# schematicFingerprint.net
KiCad netlist of a schematic drawn in Altium Designer
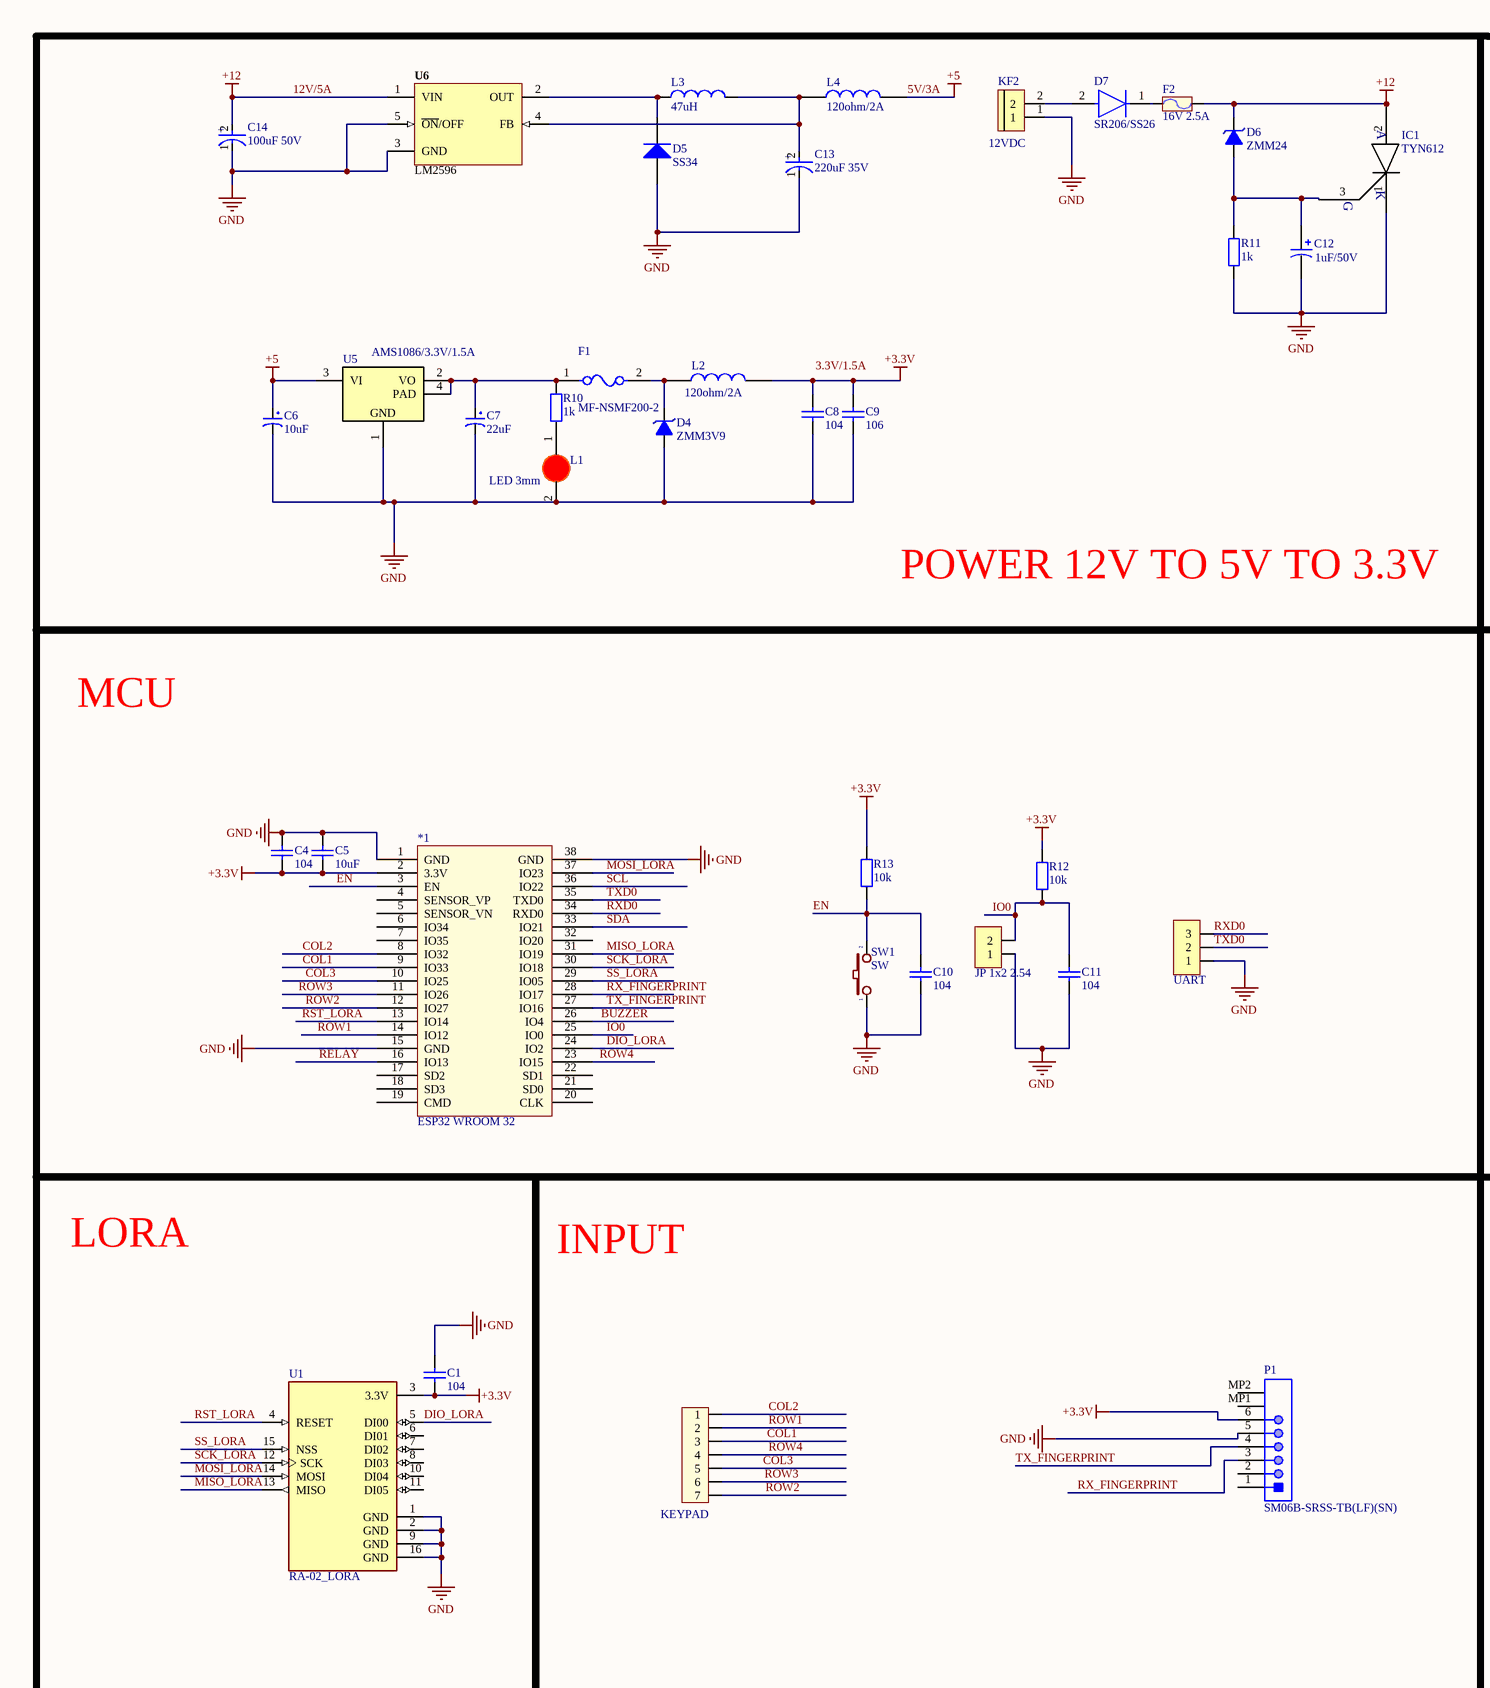
[diagram p0: schematicFingerprint.SchDoc, left]
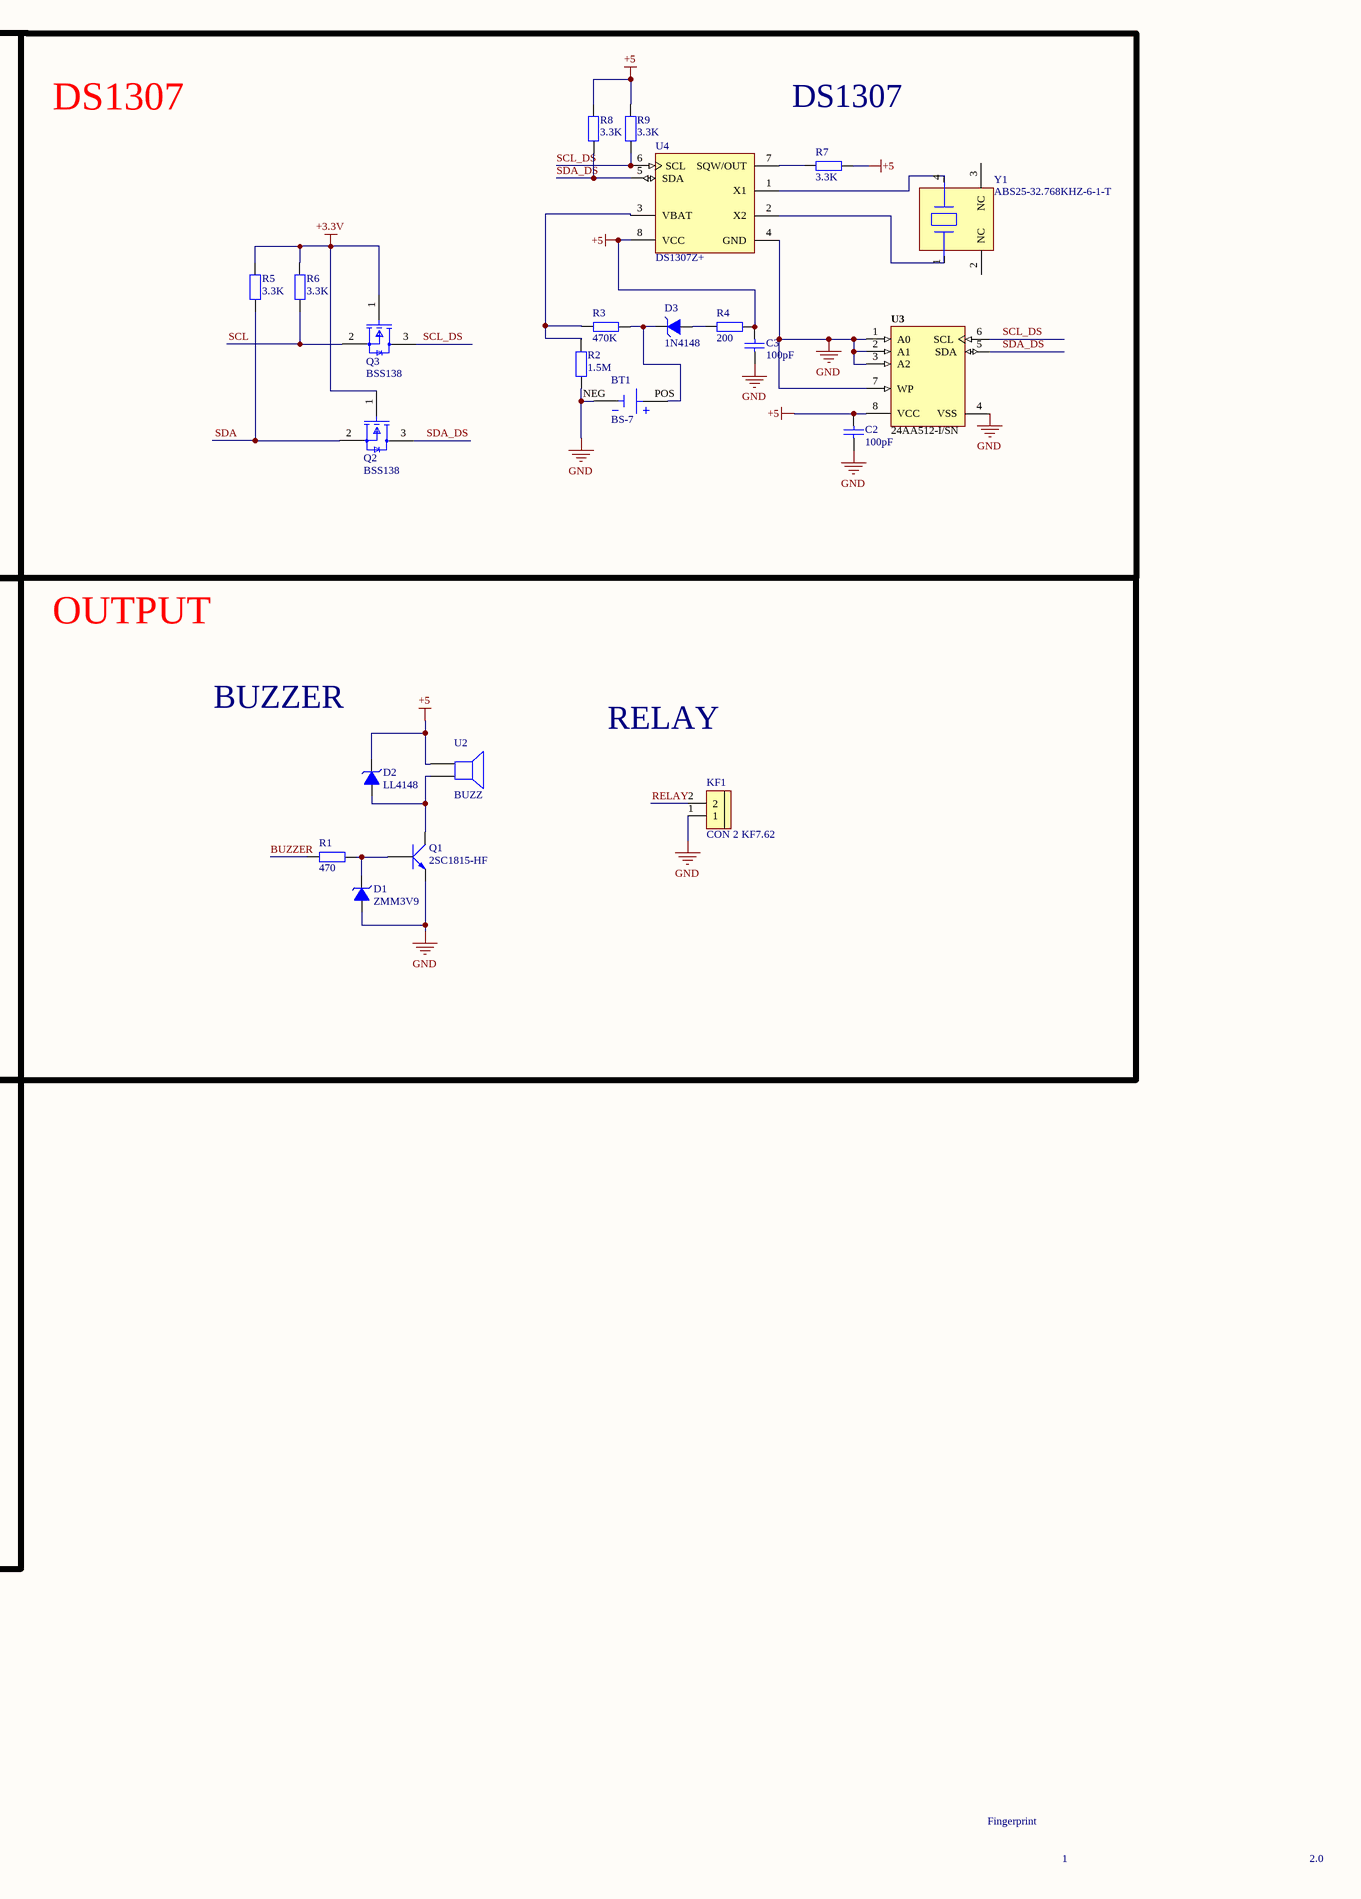
[diagram p1: schematicFingerprint.SchDoc, right]

(export (version "E")
  (design (tool "Eeschema 10.0.6"))
  (components
    (comp (ref "*1")
      (value "ESP32 WROOM 32")
      (footprint "ESP32-WROOM-32D")
      (libsource (lib "Altium_Lib_by_KhueNguyenCreator") (part "ESP32 WROOM 32"))
    )
    (comp (ref "BT1")
      (value "BS-7")
      (footprint "BAT_BS-7")
      (description "BATTERY HOLDER COIN 20MM PC PIN")
      (fields (field (name "MF") "MPD _Memory"))
      (libsource (lib "Integrated_Library") (part "BS-7"))
    )
    (comp (ref "C1")
      (value "104")
      (footprint "tu 0805")
      (description "Dán")
      (libsource (lib "Altium_Lib_by_KhueNguyenCreator") (part "Tu 0805 104 50V 10%"))
    )
    (comp (ref "C2")
      (value "100pF")
      (footprint "tu 0805")
      (description "Dán")
      (libsource (lib "Altium_Lib_by_KhueNguyenCreator") (part "Tu 0805 104 50V 10%"))
    )
    (comp (ref "C3")
      (value "100pF")
      (footprint "tu 0805")
      (description "Dán")
      (libsource (lib "Altium_Lib_by_KhueNguyenCreator") (part "Tu 0805 104 50V 10%"))
    )
    (comp (ref "C4")
      (value "104")
      (footprint "tu 0805")
      (description "Dán")
      (libsource (lib "Altium_Lib_by_KhueNguyenCreator") (part "Tu 0805 104 50V 10%"))
    )
    (comp (ref "C5")
      (value "10uF")
      (footprint "tu 0805")
      (description "Dán")
      (libsource (lib "Altium_Lib_by_KhueNguyenCreator") (part "Tu 0805 104 50V 10%"))
    )
    (comp (ref "C6")
      (value "10uF")
      (footprint "tu tantalum smd6032")
      (description "Dán")
      (libsource (lib "Altium_Lib_by_KhueNguyenCreator") (part "Tu tantalum 10uF 35V SMD6032"))
    )
    (comp (ref "C7")
      (value "22uF")
      (footprint "tu tantalum smd6032")
      (description "Dán")
      (libsource (lib "Altium_Lib_by_KhueNguyenCreator") (part "Tu tantalum 22uF 25V SMD6032"))
    )
    (comp (ref "C8")
      (value "104")
      (footprint "tu 0805")
      (description "Dán")
      (libsource (lib "Altium_Lib_by_KhueNguyenCreator") (part "Tu 0805 104 50V 10%"))
    )
    (comp (ref "C9")
      (value "106")
      (footprint "tu 0805")
      (description "Dán")
      (libsource (lib "Altium_Lib_by_KhueNguyenCreator") (part "Tu 0805 106 16V 10%"))
    )
    (comp (ref "C10")
      (value "104")
      (footprint "tu 0805")
      (description "Dán")
      (libsource (lib "Altium_Lib_by_KhueNguyenCreator") (part "Tu 0805 104 50V 10%"))
    )
    (comp (ref "C11")
      (value "104")
      (footprint "tu 0805")
      (description "Dán")
      (libsource (lib "Altium_Lib_by_KhueNguyenCreator") (part "Tu 0805 104 50V 10%"))
    )
    (comp (ref "C12")
      (value "1uF/50V")
      (footprint "CAP_ALUM_SMD_4054_TYPE_B")
      (description "CAP ALUM 10uF 20% 16V SMD")
      (fields (field (name "MPN") "EEE-HA1C100P") (field (name "MFR") "Panasonic"))
      (libsource (lib "BYTECH_HW_LIB_2019 ") (part "EEE-HA1C100P"))
    )
    (comp (ref "C13")
      (value "220uF 35V")
      (footprint "FP-SGV8X10_5-MFG")
      (description "CAP ALUM 100UF 20% 50V SMD")
      (fields (field (name "VOLTAGE") "50V") (field (name "TOLERANCE") "20%"))
      (libsource (lib "Altium Content Vault") (part "203bc49f2ac43e59fd269a8c329ed05"))
    )
    (comp (ref "C14")
      (value "100uF 50V")
      (footprint "FP-SGV8X10_5-MFG")
      (description "CAP ALUM 100UF 20% 50V SMD")
      (fields (field (name "VOLTAGE") "50V") (field (name "TOLERANCE") "20%"))
      (libsource (lib "Altium Content Vault") (part "203bc49f2ac43e59fd269a8c329ed05"))
    )
    (comp (ref "D1")
      (value "ZMM3V9")
      (footprint "DIODE ZENNER SMD SOD80")
      (description "Dán")
      (libsource (lib "Altium_Lib_by_KhueNguyenCreator") (part "Diode Zener 3.3V"))
    )
    (comp (ref "D2")
      (value "LL4148")
      (footprint "DIODE ZENNER SMD SOD80")
      (description "Dán")
      (libsource (lib "Altium_Lib_by_KhueNguyenCreator") (part "Diode Zener 3.3V"))
    )
    (comp (ref "D3")
      (value "1N4148")
      (footprint "DIODE ZENNER SMD SOD80")
      (description "Dán")
      (libsource (lib "Altium_Lib_by_KhueNguyenCreator") (part "Diode Zener 3.3V"))
    )
    (comp (ref "D4")
      (value "ZMM3V9")
      (footprint "DIODE ZENNER SMD SOD80")
      (description "Dán")
      (libsource (lib "Altium_Lib_by_KhueNguyenCreator") (part "Diode Zener 3.3V"))
    )
    (comp (ref "D5")
      (value "SS34")
      (footprint "DIODE SMA")
      (description "Dán")
      (libsource (lib "Altium_Lib_by_KhueNguyenCreator") (part "Diode SS34 ( 1N5822 )"))
    )
    (comp (ref "D6")
      (value "ZMM24")
      (footprint "DIODE ZENNER SMD SOD80")
      (description "Dán")
      (libsource (lib "Altium_Lib_by_KhueNguyenCreator") (part "Diode Zener 15V"))
    )
    (comp (ref "D7")
      (value "SR206/SS26")
      (footprint "FP-95401-MFG")
      (description "DIODE GEN PURP 600V 2A DO214AA")
      (libsource (lib "Altium Content Vault") (part "d7152d700b627762746794eb795d46e"))
    )
    (comp (ref "F1")
      (value "MF-NSMF200-2")
      (footprint "FP-MF-NSMF200-2-MFG")
      (description "PTC RESET FUSE 6V 2A 1206")
      (fields
        (field (name "MANUFACTURER") "Bourns Inc.")
        (field (name "OCTOPART") "https://octopart.com/mf-nsmf200-2-bourns-90790")
      )
      (libsource (lib "Altium Content Vault") (part "5bcf9b9f640e542cf0359d10258e979"))
    )
    (comp (ref "F2")
      (value "16V 2.5A")
      (footprint "Cau chi tu phuc hoi 2A 24V SMD1812")
      (description "2A 24V SMD1812")
      (libsource (lib "Altium_Lib_by_KhueNguyenCreator") (part "Cau chi tu phuc hoi 2A 24V SMD1812"))
    )
    (comp (ref "H1")
      (value "KEYPAD")
      (footprint "Header 7P DC 2.54")
      (description "Cắm")
      (libsource (lib "Altium_Lib_by_KhueNguyenCreator") (part "Header 7P 2.54 Duc Cong"))
    )
    (comp (ref "IC1")
      (value "TYN612")
      (footprint "PCBComponent_1")
      (libsource (lib "Integrated_Library1") (part "TYN612"))
    )
    (comp (ref "JP1")
      (value "JP 1x2 2.54")
      (footprint "JP 1x2 DT")
      (description "Cắm")
      (libsource (lib "Altium_Lib_by_KhueNguyenCreator") (part "JP 1x2 2.54 Duc Thang"))
    )
    (comp (ref "JP2")
      (value "UART")
      (footprint "JP 1x3 DT")
      (description "Cắm")
      (libsource (lib "Altium_Lib_by_KhueNguyenCreator") (part "JP 1x3 2.54 Duc Thang"))
    )
    (comp (ref "KF1")
      (value "CON 2 KF7.62")
      (footprint "CON 2 KF7.62")
      (description "Cắm")
      (libsource (lib "Altium_Lib_by_KhueNguyenCreator") (part "CON 2 KF7.62"))
    )
    (comp (ref "KF2")
      (value "12VDC")
      (footprint "CON 2 KF7.62")
      (description "Cắm")
      (libsource (lib "") (part "CON 2 KF7.62_1"))
    )
    (comp (ref "L1")
      (value "LED 3mm")
      (footprint "LED-3MM-RED")
      (description "Cắm")
      (libsource (lib "Altium_Lib_by_KhueNguyenCreator") (part "LED 3mm Do"))
    )
    (comp (ref "L2")
      (value "120ohm/2A")
      (footprint "IND-0805 (2012)")
      (description "2A 120 OHM 0805")
      (fields (field (name "MPN") "742792042"))
      (libsource (lib "BYTECH_HW_LIB_2019 ") (part "742792042"))
    )
    (comp (ref "L3")
      (value "47uH")
      (footprint "SUMI-CDRH127_V")
      (description "Power Inductor, 10 uH, +/- 20%, -40 to 100 degC, 2-Pin SMD, RoHS, Tape and Reel")
      (fields (field (name "MANUFACTURER") "Sumida") (field (name "TOLERANCE") "±20%"))
      (libsource (lib "Altium Content Vault") (part "IND-2"))
    )
    (comp (ref "L4")
      (value "120ohm/2A")
      (footprint "IND-0805 (2012)")
      (description "2A 120 OHM 0805")
      (fields (field (name "MPN") "742792042"))
      (libsource (lib "BYTECH_HW_LIB_2019 ") (part "742792042"))
    )
    (comp (ref "P1")
      (value "SM06B-SRSS-TB(LF)(SN)")
      (footprint "JST-SM06B-SRSS-TB_V")
      (description "Male Header, Pitch 1 mm, 1 x 6 Position, Height 2.95 mm, -25 to 85 degC, RoHS, Tape and Reel")
      (fields (field (name "MANUFACTURER") "JST"))
      (libsource (lib "Altium Content Vault") (part "CN-1P-2M-R6"))
    )
    (comp (ref "Q1")
      (value "2SC1815-HF")
      (footprint "SOT23")
      (description "NPN transistor")
      (libsource (lib "Altium_Lib_by_KhueNguyenCreator") (part "C1815 HF SMD"))
    )
    (comp (ref "Q2")
      (value "BSS138")
      (footprint "FP-318-08-IPC_A")
      (description "MOSFET N-CH 50V 220MA SOT-23")
      (libsource (lib "Altium Content Vault") (part "3b9c635fedb024a5347a57b145af9cc"))
    )
    (comp (ref "Q3")
      (value "BSS138")
      (footprint "FP-318-08-IPC_A")
      (description "MOSFET N-CH 50V 220MA SOT-23")
      (libsource (lib "Altium Content Vault") (part "3b9c635fedb024a5347a57b145af9cc"))
    )
    (comp (ref "R1")
      (value "470")
      (footprint "tro smd 0805")
      (description "Dán")
      (libsource (lib "Altium_Lib_by_KhueNguyenCreator") (part "Tro 0805 1% 470k"))
    )
    (comp (ref "R2")
      (value "1.5M")
      (footprint "tro smd 0805")
      (description "Dán")
      (libsource (lib "Altium_Lib_by_KhueNguyenCreator") (part "Tro 0805 5% 10k"))
    )
    (comp (ref "R3")
      (value "470K")
      (footprint "tro smd 0805")
      (description "Dán")
      (libsource (lib "Altium_Lib_by_KhueNguyenCreator") (part "Tro 0805 5% 10k"))
    )
    (comp (ref "R4")
      (value "200")
      (footprint "tro smd 0805")
      (description "Dán")
      (libsource (lib "Altium_Lib_by_KhueNguyenCreator") (part "Tro 0805 5% 10k"))
    )
    (comp (ref "R5")
      (value "3.3K")
      (footprint "tro smd 0805")
      (description "Dán")
      (libsource (lib "Altium_Lib_by_KhueNguyenCreator") (part "Tro 0805 5% 10k"))
    )
    (comp (ref "R6")
      (value "3.3K")
      (footprint "tro smd 0805")
      (description "Dán")
      (libsource (lib "Altium_Lib_by_KhueNguyenCreator") (part "Tro 0805 5% 10k"))
    )
    (comp (ref "R7")
      (value "3.3K")
      (footprint "tro smd 0805")
      (description "Dán")
      (libsource (lib "Altium_Lib_by_KhueNguyenCreator") (part "Tro 0805 5% 10k"))
    )
    (comp (ref "R8")
      (value "3.3K")
      (footprint "tro smd 0805")
      (description "Dán")
      (libsource (lib "Altium_Lib_by_KhueNguyenCreator") (part "Tro 0805 5% 10k"))
    )
    (comp (ref "R9")
      (value "3.3K")
      (footprint "tro smd 0805")
      (description "Dán")
      (libsource (lib "Altium_Lib_by_KhueNguyenCreator") (part "Tro 0805 5% 10k"))
    )
    (comp (ref "R10")
      (value "1k")
      (footprint "tro smd 0805")
      (description "Dán")
      (libsource (lib "Altium_Lib_by_KhueNguyenCreator") (part "Tro 0805 1% 1k"))
    )
    (comp (ref "R11")
      (value "1k")
      (footprint "tro smd 0805")
      (description "Dán")
      (libsource (lib "Altium_Lib_by_KhueNguyenCreator") (part "Tro 0805 1% 1k"))
    )
    (comp (ref "R12")
      (value "10k")
      (footprint "tro smd 0805")
      (description "Dán")
      (libsource (lib "Altium_Lib_by_KhueNguyenCreator") (part "Tro 0805 5% 10k"))
    )
    (comp (ref "R13")
      (value "10k")
      (footprint "tro smd 0805")
      (description "Dán")
      (libsource (lib "Altium_Lib_by_KhueNguyenCreator") (part "Tro 0805 5% 10k"))
    )
    (comp (ref "SW1")
      (value "SW")
      (footprint "SW1-SMD")
      (description "Switch button 2 pin")
      (libsource (lib "TechMT.VN_Lib_Project v2") (part "SW2"))
    )
    (comp (ref "U1")
      (value "RA-02_LORA")
      (footprint "MODULE_RA-02_LORA")
      (description "Ra-02 LoRa RF M5Stack Platform Evaluation Expansion Board")
      (fields (field (name "MP") "Ra-02 LoRa") (field (name "MF") "AI-Thinker"))
      (libsource (lib "Integrated_Library1") (part "RA-02_LORA"))
    )
    (comp (ref "U2")
      (value "BUZZ")
      (footprint "BUZZER_through_hole")
      (description "Loudspeaker")
      (libsource (lib "BYTECH_HW_LIB_2019 ") (part "Speaker"))
    )
    (comp (ref "U3")
      (value "24AA512-I/SN")
      (footprint "SO8")
      (description "512K bits I2C™ Serial EEPROM, 1.7 to 5.5 V, 400 kHz, -40 to 85 degC, 8-pin SOIC (SN8), Tube")
      (fields (field (name "MANUFACTURER") "Microchip"))
      (libsource (lib "TechMT.VN_Lib_Project v2") (part "24-AA-FC512-SOIC-TSSOP-8"))
    )
    (comp (ref "U4")
      (value "DS1307Z+")
      (footprint "S8+2_L")
      (description "64 x 8, Serial, I2C Real-Time Clock, 5.0V, 8-Pin SO, 0 to 70 degC, Pb-Free")
      (libsource (lib "Altium Content Vault") (part "PR_RTC_DS1307-IL8"))
    )
    (comp (ref "U5")
      (value "AMS1086/3.3V/1.5A")
      (footprint "TO-263-3_102_433_181X45_SMD")
      (description "Linear Voltage Regulator IC 1 Output 5A DDPAK/TO-263-3")
      (fields
        (field (name "MANUFACTURER") "STMicroelectronics")
        (field (name "MANUFACTURER PART NUMBER") "LM1084ISX-3.3/NOPB")
      )
      (libsource (lib "Altium_Lib_by_KhueNguyenCreator") (part "REG_27V-3.3V-5A-30W-TO-263_1"))
    )
    (comp (ref "U6")
      (value "LM2596")
      (footprint "TO263")
      (libsource (lib "TechMT.VN_Lib_Project v2") (part "LM2596"))
    )
    (comp (ref "Y1")
      (value "ABS25-32.768KHZ-6-1-T")
      (footprint "FP-ABS25-MFG")
      (description "CRYSTAL 32.7680KHZ 6PF SMD")
      (fields (field (name "TOLERANCE") "10ppm"))
      (libsource (lib "Altium Content Vault") (part "28be33c29b20f54059194caee89ade4"))
    )
  )
  (nets
    (net (code "1") (name "+3.3V") (class "Default")
      (node (ref "*1") (pin "2") (pinfunction "3.3V_2") (pintype "passive"))
      (node (ref "C1") (pin "2") (pinfunction "2_2") (pintype "passive"))
      (node (ref "C4") (pin "1") (pinfunction "1_1") (pintype "passive"))
      (node (ref "C5") (pin "1") (pinfunction "1_1") (pintype "passive"))
      (node (ref "C8") (pin "1") (pinfunction "1_1") (pintype "passive"))
      (node (ref "C9") (pin "1") (pinfunction "1_1") (pintype "passive"))
      (node (ref "L2") (pin "2") (pinfunction "2_2") (pintype "passive"))
      (node (ref "P1") (pin "6") (pinfunction "6_6") (pintype "passive"))
      (node (ref "Q2") (pin "1") (pinfunction "G_1") (pintype "passive"))
      (node (ref "Q3") (pin "1") (pinfunction "G_1") (pintype "passive"))
      (node (ref "R12") (pin "1") (pinfunction "1_1") (pintype "passive"))
      (node (ref "R13") (pin "1") (pinfunction "1_1") (pintype "passive"))
      (node (ref "R5") (pin "1") (pinfunction "1_1") (pintype "passive"))
      (node (ref "R6") (pin "1") (pinfunction "1_1") (pintype "passive"))
      (node (ref "U1") (pin "3") (pinfunction "3.3V_3") (pintype "power_in"))
    )
    (net (code "2") (name "+5") (class "Default")
      (node (ref "C2") (pin "2") (pinfunction "2_2") (pintype "passive"))
      (node (ref "C3") (pin "2") (pinfunction "2_2") (pintype "passive"))
      (node (ref "C6") (pin "1") (pinfunction "1_1") (pintype "passive"))
      (node (ref "D2") (pin "2") (pinfunction "K_2") (pintype "passive"))
      (node (ref "L4") (pin "2") (pinfunction "2_2") (pintype "passive"))
      (node (ref "R4") (pin "2") (pinfunction "2_2") (pintype "passive"))
      (node (ref "R7") (pin "2") (pinfunction "2_2") (pintype "passive"))
      (node (ref "R8") (pin "1") (pinfunction "1_1") (pintype "passive"))
      (node (ref "R9") (pin "1") (pinfunction "1_1") (pintype "passive"))
      (node (ref "U2") (pin "1") (pinfunction "1_1") (pintype "passive"))
      (node (ref "U3") (pin "8") (pinfunction "VCC_8") (pintype "power_in"))
      (node (ref "U4") (pin "8") (pinfunction "VCC_8") (pintype "power_in"))
      (node (ref "U5") (pin "3") (pinfunction "VI_3") (pintype "passive"))
    )
    (net (code "3") (name "+12") (class "Default")
      (node (ref "C14") (pin "2") (pinfunction "A_2") (pintype "passive"))
      (node (ref "D6") (pin "2") (pinfunction "K_2") (pintype "passive"))
      (node (ref "F2") (pin "2") (pinfunction "2_2") (pintype "passive"))
      (node (ref "IC1") (pin "2") (pinfunction "A_2") (pintype "passive"))
      (node (ref "U6") (pin "1") (pinfunction "VIN_1") (pintype "power_in"))
    )
    (net (code "5") (name "/BUZZER") (class "Default")
      (node (ref "*1") (pin "26") (pinfunction "IO4_26") (pintype "passive"))
      (node (ref "R1") (pin "1") (pinfunction "1_1") (pintype "passive"))
    )
    (net (code "6") (name "/COL1") (class "Default")
      (node (ref "*1") (pin "9") (pinfunction "IO33_9") (pintype "passive"))
      (node (ref "H1") (pin "3") (pinfunction "3_3") (pintype "passive"))
    )
    (net (code "7") (name "/COL2") (class "Default")
      (node (ref "*1") (pin "8") (pinfunction "IO32_8") (pintype "passive"))
      (node (ref "H1") (pin "1") (pinfunction "1_1") (pintype "passive"))
    )
    (net (code "8") (name "/COL3") (class "Default")
      (node (ref "*1") (pin "10") (pinfunction "IO25_10") (pintype "passive"))
      (node (ref "H1") (pin "5") (pinfunction "5_5") (pintype "passive"))
    )
    (net (code "9") (name "/DIO_LORA") (class "Default")
      (node (ref "*1") (pin "24") (pinfunction "IO2_24") (pintype "passive"))
      (node (ref "U1") (pin "5") (pinfunction "DI00_5") (pintype "bidirectional"))
    )
    (net (code "10") (name "/EN") (class "Default")
      (node (ref "*1") (pin "3") (pinfunction "EN_3") (pintype "passive"))
      (node (ref "C10") (pin "2") (pinfunction "2_2") (pintype "passive"))
      (node (ref "R13") (pin "2") (pinfunction "2_2") (pintype "passive"))
      (node (ref "SW1") (pin "2") (pinfunction "2_2") (pintype "passive"))
    )
    (net (code "11") (name "/IO0") (class "Default")
      (node (ref "*1") (pin "25") (pinfunction "IO0_25") (pintype "passive"))
      (node (ref "C11") (pin "2") (pinfunction "2_2") (pintype "passive"))
      (node (ref "JP1") (pin "2") (pinfunction "2_2") (pintype "passive"))
      (node (ref "R12") (pin "2") (pinfunction "2_2") (pintype "passive"))
    )
    (net (code "12") (name "/MISO_LORA") (class "Default")
      (node (ref "*1") (pin "31") (pinfunction "IO19_31") (pintype "passive"))
      (node (ref "U1") (pin "13") (pinfunction "MISO_13") (pintype "output"))
    )
    (net (code "13") (name "/MOSI_LORA") (class "Default")
      (node (ref "*1") (pin "37") (pinfunction "IO23_37") (pintype "passive"))
      (node (ref "U1") (pin "14") (pinfunction "MOSI_14") (pintype "input"))
    )
    (net (code "14") (name "/RELAY") (class "Default")
      (node (ref "*1") (pin "16") (pinfunction "IO13_16") (pintype "passive"))
      (node (ref "KF1") (pin "2") (pinfunction "2_2") (pintype "passive"))
    )
    (net (code "15") (name "/ROW1") (class "Default")
      (node (ref "*1") (pin "14") (pinfunction "IO12_14") (pintype "passive"))
      (node (ref "H1") (pin "2") (pinfunction "2_2") (pintype "passive"))
    )
    (net (code "16") (name "/ROW2") (class "Default")
      (node (ref "*1") (pin "12") (pinfunction "IO27_12") (pintype "passive"))
      (node (ref "H1") (pin "7") (pinfunction "7_7") (pintype "passive"))
    )
    (net (code "17") (name "/ROW3") (class "Default")
      (node (ref "*1") (pin "11") (pinfunction "IO26_11") (pintype "passive"))
      (node (ref "H1") (pin "6") (pinfunction "6_6") (pintype "passive"))
    )
    (net (code "18") (name "/ROW4") (class "Default")
      (node (ref "*1") (pin "23") (pinfunction "IO15_23") (pintype "passive"))
      (node (ref "H1") (pin "4") (pinfunction "4_4") (pintype "passive"))
    )
    (net (code "19") (name "/RST_LORA") (class "Default")
      (node (ref "*1") (pin "13") (pinfunction "IO14_13") (pintype "passive"))
      (node (ref "U1") (pin "4") (pinfunction "RESET_4") (pintype "input"))
    )
    (net (code "20") (name "/RXD0") (class "Default")
      (node (ref "*1") (pin "34") (pinfunction "RXD0_34") (pintype "passive"))
      (node (ref "JP2") (pin "3") (pinfunction "3_3") (pintype "passive"))
    )
    (net (code "21") (name "/RX_FINGERPRINT") (class "Default")
      (node (ref "*1") (pin "28") (pinfunction "IO17_28") (pintype "passive"))
      (node (ref "P1") (pin "3") (pinfunction "3_3") (pintype "passive"))
    )
    (net (code "22") (name "/SCK_LORA") (class "Default")
      (node (ref "*1") (pin "30") (pinfunction "IO18_30") (pintype "passive"))
      (node (ref "U1") (pin "12") (pinfunction "SCK_12") (pintype "input"))
    )
    (net (code "23") (name "/SCL") (class "Default")
      (node (ref "*1") (pin "36") (pinfunction "IO22_36") (pintype "passive"))
      (node (ref "Q3") (pin "2") (pinfunction "S_2") (pintype "passive"))
      (node (ref "R6") (pin "2") (pinfunction "2_2") (pintype "passive"))
    )
    (net (code "24") (name "/SCL_DS") (class "Default")
      (node (ref "Q3") (pin "3") (pinfunction "D_3") (pintype "passive"))
      (node (ref "R9") (pin "2") (pinfunction "2_2") (pintype "passive"))
      (node (ref "U3") (pin "6") (pinfunction "SCL_6") (pintype "input"))
      (node (ref "U4") (pin "6") (pinfunction "SCL_6") (pintype "input"))
    )
    (net (code "25") (name "/SDA") (class "Default")
      (node (ref "*1") (pin "33") (pinfunction "IO21_33") (pintype "passive"))
      (node (ref "Q2") (pin "2") (pinfunction "S_2") (pintype "passive"))
      (node (ref "R5") (pin "2") (pinfunction "2_2") (pintype "passive"))
    )
    (net (code "26") (name "/SDA_DS") (class "Default")
      (node (ref "Q2") (pin "3") (pinfunction "D_3") (pintype "passive"))
      (node (ref "R8") (pin "2") (pinfunction "2_2") (pintype "passive"))
      (node (ref "U3") (pin "5") (pinfunction "SDA_5") (pintype "bidirectional"))
      (node (ref "U4") (pin "5") (pinfunction "SDA_5") (pintype "bidirectional"))
    )
    (net (code "27") (name "/SS_LORA") (class "Default")
      (node (ref "*1") (pin "29") (pinfunction "IO05_29") (pintype "passive"))
      (node (ref "U1") (pin "15") (pinfunction "NSS_15") (pintype "input"))
    )
    (net (code "28") (name "/TXD0") (class "Default")
      (node (ref "*1") (pin "35") (pinfunction "TXD0_35") (pintype "passive"))
      (node (ref "JP2") (pin "2") (pinfunction "2_2") (pintype "passive"))
    )
    (net (code "29") (name "/TX_FINGERPRINT") (class "Default")
      (node (ref "*1") (pin "27") (pinfunction "IO16_27") (pintype "passive"))
      (node (ref "P1") (pin "4") (pinfunction "4_4") (pintype "passive"))
    )
    (net (code "30") (name "GND") (class "Default")
      (node (ref "*1") (pin "1") (pinfunction "GND_1") (pintype "passive"))
      (node (ref "*1") (pin "15") (pinfunction "GND_15") (pintype "passive"))
      (node (ref "*1") (pin "38") (pinfunction "GND_38") (pintype "passive"))
      (node (ref "BT1") (pin "NEG") (pinfunction "NEG_NEG") (pintype "passive"))
      (node (ref "C1") (pin "1") (pinfunction "1_1") (pintype "passive"))
      (node (ref "C10") (pin "1") (pinfunction "1_1") (pintype "passive"))
      (node (ref "C11") (pin "1") (pinfunction "1_1") (pintype "passive"))
      (node (ref "C12") (pin "2") (pinfunction "2_2") (pintype "passive"))
      (node (ref "C13") (pin "1") (pinfunction "C_1") (pintype "passive"))
      (node (ref "C14") (pin "1") (pinfunction "C_1") (pintype "passive"))
      (node (ref "C2") (pin "1") (pinfunction "1_1") (pintype "passive"))
      (node (ref "C3") (pin "1") (pinfunction "1_1") (pintype "passive"))
      (node (ref "C4") (pin "2") (pinfunction "2_2") (pintype "passive"))
      (node (ref "C5") (pin "2") (pinfunction "2_2") (pintype "passive"))
      (node (ref "C6") (pin "2") (pinfunction "2_2") (pintype "passive"))
      (node (ref "C7") (pin "2") (pinfunction "2_2") (pintype "passive"))
      (node (ref "C8") (pin "2") (pinfunction "2_2") (pintype "passive"))
      (node (ref "C9") (pin "2") (pinfunction "2_2") (pintype "passive"))
      (node (ref "D1") (pin "1") (pinfunction "A_1") (pintype "passive"))
      (node (ref "D4") (pin "1") (pinfunction "A_1") (pintype "passive"))
      (node (ref "D5") (pin "1") (pinfunction "A_1") (pintype "passive"))
      (node (ref "IC1") (pin "1") (pinfunction "K_1") (pintype "passive"))
      (node (ref "JP1") (pin "1") (pinfunction "1_1") (pintype "passive"))
      (node (ref "JP2") (pin "1") (pinfunction "1_1") (pintype "passive"))
      (node (ref "KF1") (pin "1") (pinfunction "1_1") (pintype "passive"))
      (node (ref "KF2") (pin "1") (pinfunction "1_1") (pintype "passive"))
      (node (ref "L1") (pin "2") (pinfunction "K_2") (pintype "passive"))
      (node (ref "P1") (pin "5") (pinfunction "5_5") (pintype "passive"))
      (node (ref "Q1") (pin "2") (pinfunction "E_2") (pintype "passive"))
      (node (ref "R11") (pin "1") (pinfunction "1_1") (pintype "passive"))
      (node (ref "R2") (pin "2") (pinfunction "2_2") (pintype "passive"))
      (node (ref "SW1") (pin "1") (pinfunction "1_1") (pintype "passive"))
      (node (ref "U1") (pin "1") (pinfunction "GND_1") (pintype "power_in"))
      (node (ref "U1") (pin "16") (pinfunction "GND_16") (pintype "power_in"))
      (node (ref "U1") (pin "2") (pinfunction "GND_2") (pintype "power_in"))
      (node (ref "U1") (pin "9") (pinfunction "GND_9") (pintype "power_in"))
      (node (ref "U3") (pin "1") (pinfunction "A0_1") (pintype "input"))
      (node (ref "U3") (pin "2") (pinfunction "A1_2") (pintype "input"))
      (node (ref "U3") (pin "3") (pinfunction "A2_3") (pintype "input"))
      (node (ref "U3") (pin "4") (pinfunction "VSS_4") (pintype "power_in"))
      (node (ref "U3") (pin "7") (pinfunction "WP_7") (pintype "input"))
      (node (ref "U4") (pin "4") (pinfunction "GND_4") (pintype "power_in"))
      (node (ref "U5") (pin "1") (pintype "passive"))
      (node (ref "U6") (pin "3") (pinfunction "GND_3") (pintype "power_in"))
      (node (ref "U6") (pin "5") (pinfunction "~{ON}/OFF_5") (pintype "input"))
    )
    (net (code "31") (name "Net-(C13-A)") (class "Default")
      (node (ref "C13") (pin "2") (pinfunction "A_2") (pintype "passive"))
      (node (ref "L3") (pin "2") (pinfunction "2_2") (pintype "passive"))
      (node (ref "L4") (pin "1") (pinfunction "1_1") (pintype "passive"))
      (node (ref "U6") (pin "4") (pinfunction "FB_4") (pintype "input"))
    )
    (net (code "32") (name "Net-(D1-K)") (class "Default")
      (node (ref "D1") (pin "2") (pinfunction "K_2") (pintype "passive"))
      (node (ref "Q1") (pin "1") (pinfunction "B_1") (pintype "passive"))
      (node (ref "R1") (pin "2") (pinfunction "2_2") (pintype "passive"))
    )
    (net (code "33") (name "Net-(D2-A)") (class "Default")
      (node (ref "D2") (pin "1") (pinfunction "A_1") (pintype "passive"))
      (node (ref "Q1") (pin "3") (pinfunction "C_3") (pintype "passive"))
      (node (ref "U2") (pin "2") (pinfunction "2_2") (pintype "passive"))
    )
    (net (code "34") (name "Net-(D3-A)") (class "Default")
      (node (ref "D3") (pin "1") (pinfunction "A_1") (pintype "passive"))
      (node (ref "R4") (pin "1") (pinfunction "1_1") (pintype "passive"))
    )
    (net (code "35") (name "Net-(D3-K)") (class "Default")
      (node (ref "BT1") (pin "POS") (pinfunction "POS_POS") (pintype "passive"))
      (node (ref "D3") (pin "2") (pinfunction "K_2") (pintype "passive"))
      (node (ref "R3") (pin "2") (pinfunction "2_2") (pintype "passive"))
    )
    (net (code "36") (name "Net-(D4-K)") (class "Default")
      (node (ref "D4") (pin "2") (pinfunction "K_2") (pintype "passive"))
      (node (ref "F1") (pin "2") (pinfunction "2_2") (pintype "passive"))
      (node (ref "L2") (pin "1") (pinfunction "1_1") (pintype "passive"))
    )
    (net (code "37") (name "Net-(D5-K)") (class "Default")
      (node (ref "D5") (pin "2") (pinfunction "K_2") (pintype "passive"))
      (node (ref "L3") (pin "1") (pinfunction "1_1") (pintype "passive"))
      (node (ref "U6") (pin "2") (pinfunction "OUT_2") (pintype "power_in"))
    )
    (net (code "38") (name "Net-(D6-A)") (class "Default")
      (node (ref "C12") (pin "1") (pinfunction "1_1") (pintype "passive"))
      (node (ref "D6") (pin "1") (pinfunction "A_1") (pintype "passive"))
      (node (ref "IC1") (pin "3") (pinfunction "G_3") (pintype "passive"))
      (node (ref "R11") (pin "2") (pinfunction "2_2") (pintype "passive"))
    )
    (net (code "39") (name "Net-(D7-A)") (class "Default")
      (node (ref "D7") (pin "2") (pinfunction "A_2") (pintype "passive"))
      (node (ref "KF2") (pin "2") (pinfunction "2_2") (pintype "passive"))
    )
    (net (code "40") (name "Net-(D7-C)") (class "Default")
      (node (ref "D7") (pin "1") (pinfunction "C_1") (pintype "passive"))
      (node (ref "F2") (pin "1") (pinfunction "1_1") (pintype "passive"))
    )
    (net (code "41") (name "Net-(L1-A)") (class "Default")
      (node (ref "L1") (pin "1") (pinfunction "A_1") (pintype "passive"))
      (node (ref "R10") (pin "2") (pinfunction "2_2") (pintype "passive"))
    )
    (net (code "42") (name "Net-(U4-SQW{slash}OUT)") (class "Default")
      (node (ref "R7") (pin "1") (pinfunction "1_1") (pintype "passive"))
      (node (ref "U4") (pin "7") (pinfunction "SQW/OUT_7") (pintype "open_collector"))
    )
    (net (code "43") (name "Net-(U4-VBAT)") (class "Default")
      (node (ref "R2") (pin "1") (pinfunction "1_1") (pintype "passive"))
      (node (ref "R3") (pin "1") (pinfunction "1_1") (pintype "passive"))
      (node (ref "U4") (pin "3") (pinfunction "VBAT_3") (pintype "power_in"))
    )
    (net (code "44") (name "Net-(U4-X1)") (class "Default")
      (node (ref "U4") (pin "1") (pinfunction "X1_1") (pintype "passive"))
      (node (ref "Y1") (pin "4") (pinfunction "4_4") (pintype "passive"))
    )
    (net (code "45") (name "Net-(U4-X2)") (class "Default")
      (node (ref "U4") (pin "2") (pinfunction "X2_2") (pintype "passive"))
      (node (ref "Y1") (pin "1") (pinfunction "1_1") (pintype "passive"))
    )
    (net (code "46") (name "Net-(U5-PAD)") (class "Default")
      (node (ref "C7") (pin "1") (pinfunction "1_1") (pintype "passive"))
      (node (ref "F1") (pin "1") (pinfunction "1_1") (pintype "passive"))
      (node (ref "R10") (pin "1") (pinfunction "1_1") (pintype "passive"))
      (node (ref "U5") (pin "2") (pinfunction "VO_2") (pintype "passive"))
      (node (ref "U5") (pin "4") (pinfunction "PAD_4") (pintype "passive"))
    )
    (net (code "47") (name "unconnected-(*1-CLK-Pad20)") (class "Default")
      (node (ref "*1") (pin "20") (pinfunction "CLK_20") (pintype "passive"))
    )
    (net (code "48") (name "unconnected-(*1-CMD-Pad19)") (class "Default")
      (node (ref "*1") (pin "19") (pinfunction "CMD_19") (pintype "passive"))
    )
    (net (code "49") (name "unconnected-(*1-IO20-Pad32)") (class "Default")
      (node (ref "*1") (pin "32") (pinfunction "IO20_32") (pintype "passive"))
    )
    (net (code "50") (name "unconnected-(*1-IO34-Pad6)") (class "Default")
      (node (ref "*1") (pin "6") (pinfunction "IO34_6") (pintype "passive"))
    )
    (net (code "51") (name "unconnected-(*1-IO35-Pad7)") (class "Default")
      (node (ref "*1") (pin "7") (pinfunction "IO35_7") (pintype "passive"))
    )
    (net (code "52") (name "unconnected-(*1-SD0-Pad21)") (class "Default")
      (node (ref "*1") (pin "21") (pinfunction "SD0_21") (pintype "passive"))
    )
    (net (code "53") (name "unconnected-(*1-SD1-Pad22)") (class "Default")
      (node (ref "*1") (pin "22") (pinfunction "SD1_22") (pintype "passive"))
    )
    (net (code "54") (name "unconnected-(*1-SD2-Pad17)") (class "Default")
      (node (ref "*1") (pin "17") (pinfunction "SD2_17") (pintype "passive"))
    )
    (net (code "55") (name "unconnected-(*1-SD3-Pad18)") (class "Default")
      (node (ref "*1") (pin "18") (pinfunction "SD3_18") (pintype "passive"))
    )
    (net (code "56") (name "unconnected-(*1-SENSOR_VN-Pad5)") (class "Default")
      (node (ref "*1") (pin "5") (pinfunction "SENSOR_VN_5") (pintype "passive"))
    )
    (net (code "57") (name "unconnected-(*1-SENSOR_VP-Pad4)") (class "Default")
      (node (ref "*1") (pin "4") (pinfunction "SENSOR_VP_4") (pintype "passive"))
    )
    (net (code "58") (name "unconnected-(P1-Pad1)") (class "Default")
      (node (ref "P1") (pin "1") (pinfunction "1_1") (pintype "passive"))
    )
    (net (code "59") (name "unconnected-(P1-Pad2)") (class "Default")
      (node (ref "P1") (pin "2") (pinfunction "2_2") (pintype "passive"))
    )
    (net (code "60") (name "unconnected-(P1-PadMP1)") (class "Default")
      (node (ref "P1") (pin "MP1") (pinfunction "MP1_MP1") (pintype "passive"))
    )
    (net (code "61") (name "unconnected-(P1-PadMP2)") (class "Default")
      (node (ref "P1") (pin "MP2") (pinfunction "MP2_MP2") (pintype "passive"))
    )
    (net (code "62") (name "unconnected-(U1-DI01-Pad6)") (class "Default")
      (node (ref "U1") (pin "6") (pinfunction "DI01_6") (pintype "bidirectional"))
    )
    (net (code "63") (name "unconnected-(U1-DI02-Pad7)") (class "Default")
      (node (ref "U1") (pin "7") (pinfunction "DI02_7") (pintype "bidirectional"))
    )
    (net (code "64") (name "unconnected-(U1-DI03-Pad8)") (class "Default")
      (node (ref "U1") (pin "8") (pinfunction "DI03_8") (pintype "bidirectional"))
    )
    (net (code "65") (name "unconnected-(U1-DI04-Pad10)") (class "Default")
      (node (ref "U1") (pin "10") (pinfunction "DI04_10") (pintype "bidirectional"))
    )
    (net (code "66") (name "unconnected-(U1-DI05-Pad11)") (class "Default")
      (node (ref "U1") (pin "11") (pinfunction "DI05_11") (pintype "bidirectional"))
    )
    (net (code "67") (name "unconnected-(Y1-NC-Pad2)") (class "Default")
      (node (ref "Y1") (pin "2") (pinfunction "NC_2") (pintype "passive"))
    )
    (net (code "68") (name "unconnected-(Y1-NC-Pad3)") (class "Default")
      (node (ref "Y1") (pin "3") (pinfunction "NC_3") (pintype "passive"))
    )
  )
)
